# Miscellaneous.net
KiCad netlist of a schematic drawn in Altium Designer
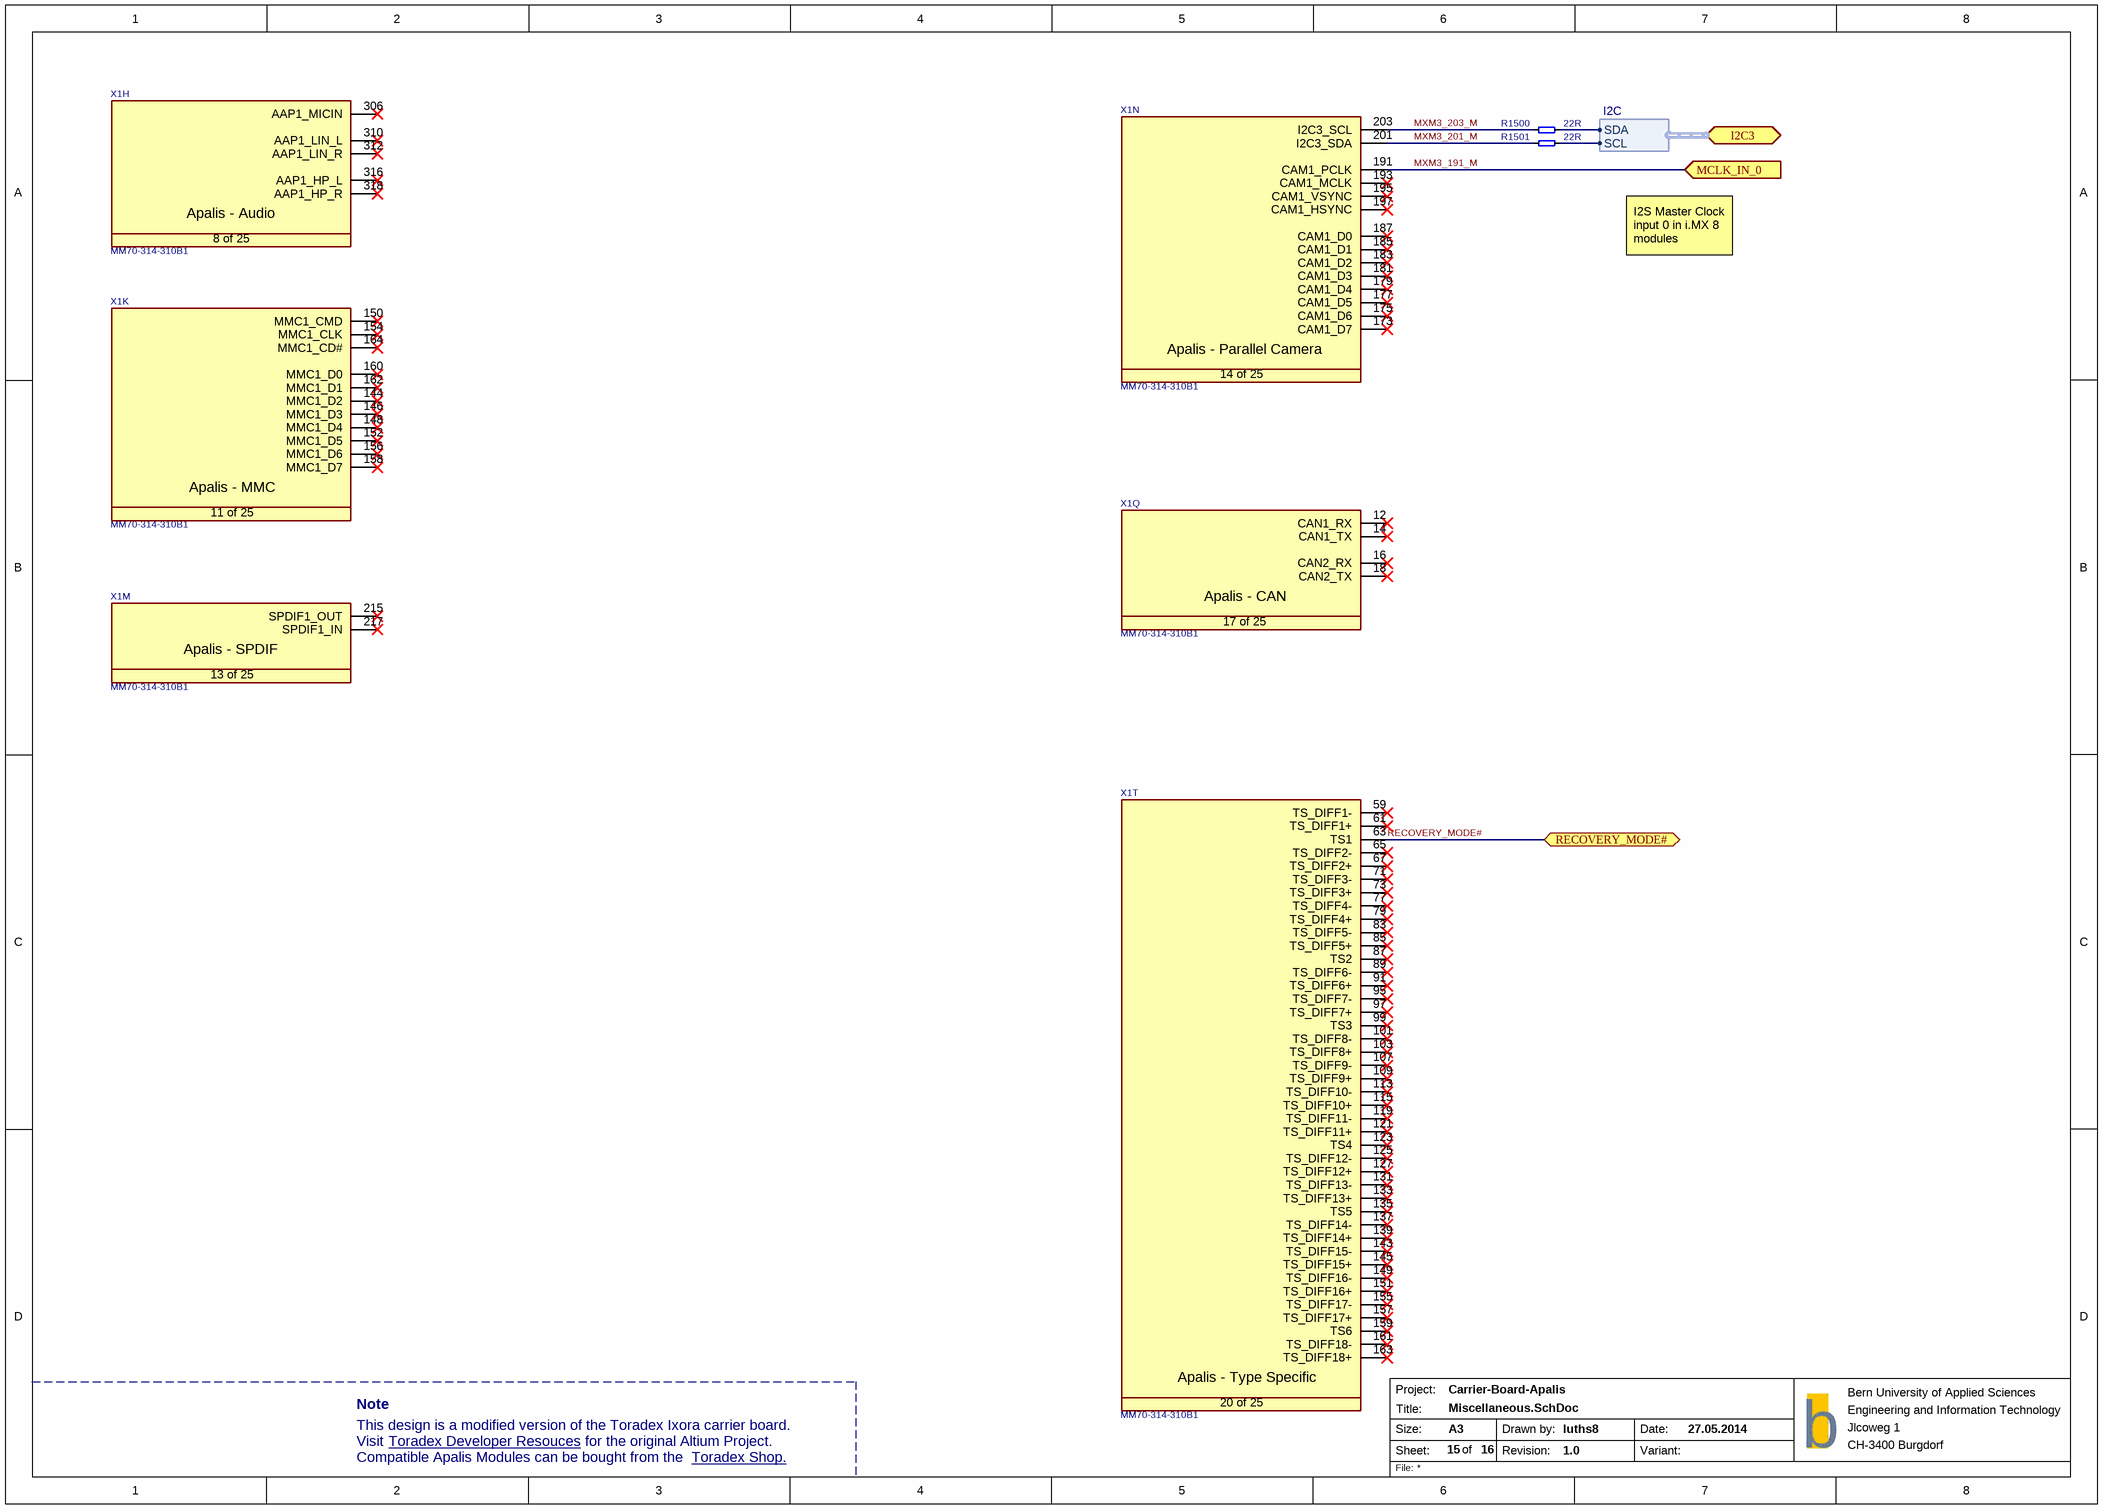
[diagram p0: Miscellaneous.SchDoc]

(export (version "E")
  (design (tool "Eeschema 10.0.6"))
  (components
    (comp (ref "R1500")
      (value "22R")
      (footprint "SMD0603RES")
      (description "Resistor 22 ohm 63mW 5% 0603")
      (fields (field (name "TOLERANCE") "5%"))
      (libsource (lib "Ixora") (part "R-22R-63mW-5%-0402"))
    )
    (comp (ref "R1501")
      (value "22R")
      (footprint "SMD0603RES")
      (description "Resistor 22 ohm 63mW 5% 0603")
      (fields (field (name "TOLERANCE") "5%"))
      (libsource (lib "Ixora") (part "R-22R-63mW-5%-0402"))
    )
    (comp (ref "X1")
      (value "CON-JAE-MM70-314-310B1-314-0.5mm")
      (footprint "T_JAE_MM70-314-310B1")
      (description "MXM3 Connector")
      (fields (field (name "MANUFACTURER PART NO.") "MM70-314-310B1"))
      (libsource (lib "Ixora") (part "CON-JAE-MM70-314-310B1-314-0.5mm"))
    )
  )
  (nets
    (net (code "2") (name "/MXM3_191_M") (class "Default")
      (node (ref "X1") (pin "191") (pinfunction "CAM1_PCLK_191") (pintype "passive"))
    )
    (net (code "3") (name "/MXM3_201_M") (class "Default")
      (node (ref "R1501") (pin "1") (pinfunction "1_1") (pintype "passive"))
      (node (ref "X1") (pin "201") (pinfunction "I2C3_SDA_201") (pintype "passive"))
    )
    (net (code "4") (name "/MXM3_203_M") (class "Default")
      (node (ref "R1500") (pin "1") (pinfunction "1_1") (pintype "passive"))
      (node (ref "X1") (pin "203") (pinfunction "I2C3_SCL_203") (pintype "passive"))
    )
    (net (code "5") (name "/RECOVERY_MODE#") (class "Default")
      (node (ref "X1") (pin "63") (pinfunction "TS1_63") (pintype "passive"))
    )
    (net (code "6") (name "/SCL") (class "Default")
      (node (ref "R1501") (pin "2") (pinfunction "2_2") (pintype "passive"))
    )
    (net (code "7") (name "/SDA") (class "Default")
      (node (ref "R1500") (pin "2") (pinfunction "2_2") (pintype "passive"))
    )
    (net (code "9") (name "unconnected-(X1H-AAP1_HP_L-Pad316)") (class "Default")
      (node (ref "X1") (pin "316") (pinfunction "AAP1_HP_L_316") (pintype "passive+no_connect"))
    )
    (net (code "10") (name "unconnected-(X1H-AAP1_HP_R-Pad318)") (class "Default")
      (node (ref "X1") (pin "318") (pinfunction "AAP1_HP_R_318") (pintype "passive+no_connect"))
    )
    (net (code "11") (name "unconnected-(X1H-AAP1_LIN_L-Pad310)") (class "Default")
      (node (ref "X1") (pin "310") (pinfunction "AAP1_LIN_L_310") (pintype "passive+no_connect"))
    )
    (net (code "12") (name "unconnected-(X1H-AAP1_LIN_R-Pad312)") (class "Default")
      (node (ref "X1") (pin "312") (pinfunction "AAP1_LIN_R_312") (pintype "passive+no_connect"))
    )
    (net (code "13") (name "unconnected-(X1H-AAP1_MICIN-Pad306)") (class "Default")
      (node (ref "X1") (pin "306") (pinfunction "AAP1_MICIN_306") (pintype "passive+no_connect"))
    )
    (net (code "14") (name "unconnected-(X1K-MMC1_CD#-Pad164)") (class "Default")
      (node (ref "X1") (pin "164") (pinfunction "MMC1_CD#_164") (pintype "passive+no_connect"))
    )
    (net (code "15") (name "unconnected-(X1K-MMC1_CLK-Pad154)") (class "Default")
      (node (ref "X1") (pin "154") (pinfunction "MMC1_CLK_154") (pintype "passive+no_connect"))
    )
    (net (code "16") (name "unconnected-(X1K-MMC1_CMD-Pad150)") (class "Default")
      (node (ref "X1") (pin "150") (pinfunction "MMC1_CMD_150") (pintype "passive+no_connect"))
    )
    (net (code "17") (name "unconnected-(X1K-MMC1_D0-Pad160)") (class "Default")
      (node (ref "X1") (pin "160") (pinfunction "MMC1_D0_160") (pintype "passive+no_connect"))
    )
    (net (code "18") (name "unconnected-(X1K-MMC1_D1-Pad162)") (class "Default")
      (node (ref "X1") (pin "162") (pinfunction "MMC1_D1_162") (pintype "passive+no_connect"))
    )
    (net (code "19") (name "unconnected-(X1K-MMC1_D2-Pad144)") (class "Default")
      (node (ref "X1") (pin "144") (pinfunction "MMC1_D2_144") (pintype "passive+no_connect"))
    )
    (net (code "20") (name "unconnected-(X1K-MMC1_D3-Pad146)") (class "Default")
      (node (ref "X1") (pin "146") (pinfunction "MMC1_D3_146") (pintype "passive+no_connect"))
    )
    (net (code "21") (name "unconnected-(X1K-MMC1_D4-Pad148)") (class "Default")
      (node (ref "X1") (pin "148") (pinfunction "MMC1_D4_148") (pintype "passive+no_connect"))
    )
    (net (code "22") (name "unconnected-(X1K-MMC1_D5-Pad152)") (class "Default")
      (node (ref "X1") (pin "152") (pinfunction "MMC1_D5_152") (pintype "passive+no_connect"))
    )
    (net (code "23") (name "unconnected-(X1K-MMC1_D6-Pad156)") (class "Default")
      (node (ref "X1") (pin "156") (pinfunction "MMC1_D6_156") (pintype "passive+no_connect"))
    )
    (net (code "24") (name "unconnected-(X1K-MMC1_D7-Pad158)") (class "Default")
      (node (ref "X1") (pin "158") (pinfunction "MMC1_D7_158") (pintype "passive+no_connect"))
    )
    (net (code "25") (name "unconnected-(X1M-SPDIF1_IN-Pad217)") (class "Default")
      (node (ref "X1") (pin "217") (pinfunction "SPDIF1_IN_217") (pintype "passive+no_connect"))
    )
    (net (code "26") (name "unconnected-(X1M-SPDIF1_OUT-Pad215)") (class "Default")
      (node (ref "X1") (pin "215") (pinfunction "SPDIF1_OUT_215") (pintype "passive+no_connect"))
    )
    (net (code "27") (name "unconnected-(X1N-CAM1_D0-Pad187)") (class "Default")
      (node (ref "X1") (pin "187") (pinfunction "CAM1_D0_187") (pintype "passive+no_connect"))
    )
    (net (code "28") (name "unconnected-(X1N-CAM1_D1-Pad185)") (class "Default")
      (node (ref "X1") (pin "185") (pinfunction "CAM1_D1_185") (pintype "passive+no_connect"))
    )
    (net (code "29") (name "unconnected-(X1N-CAM1_D2-Pad183)") (class "Default")
      (node (ref "X1") (pin "183") (pinfunction "CAM1_D2_183") (pintype "passive+no_connect"))
    )
    (net (code "30") (name "unconnected-(X1N-CAM1_D3-Pad181)") (class "Default")
      (node (ref "X1") (pin "181") (pinfunction "CAM1_D3_181") (pintype "passive+no_connect"))
    )
    (net (code "31") (name "unconnected-(X1N-CAM1_D4-Pad179)") (class "Default")
      (node (ref "X1") (pin "179") (pinfunction "CAM1_D4_179") (pintype "passive+no_connect"))
    )
    (net (code "32") (name "unconnected-(X1N-CAM1_D5-Pad177)") (class "Default")
      (node (ref "X1") (pin "177") (pinfunction "CAM1_D5_177") (pintype "passive+no_connect"))
    )
    (net (code "33") (name "unconnected-(X1N-CAM1_D6-Pad175)") (class "Default")
      (node (ref "X1") (pin "175") (pinfunction "CAM1_D6_175") (pintype "passive+no_connect"))
    )
    (net (code "34") (name "unconnected-(X1N-CAM1_D7-Pad173)") (class "Default")
      (node (ref "X1") (pin "173") (pinfunction "CAM1_D7_173") (pintype "passive+no_connect"))
    )
    (net (code "35") (name "unconnected-(X1N-CAM1_HSYNC-Pad197)") (class "Default")
      (node (ref "X1") (pin "197") (pinfunction "CAM1_HSYNC_197") (pintype "passive+no_connect"))
    )
    (net (code "36") (name "unconnected-(X1N-CAM1_MCLK-Pad193)") (class "Default")
      (node (ref "X1") (pin "193") (pinfunction "CAM1_MCLK_193") (pintype "passive+no_connect"))
    )
    (net (code "37") (name "unconnected-(X1N-CAM1_VSYNC-Pad195)") (class "Default")
      (node (ref "X1") (pin "195") (pinfunction "CAM1_VSYNC_195") (pintype "passive+no_connect"))
    )
    (net (code "38") (name "unconnected-(X1Q-CAN1_RX-Pad12)") (class "Default")
      (node (ref "X1") (pin "12") (pinfunction "CAN1_RX_12") (pintype "passive+no_connect"))
    )
    (net (code "39") (name "unconnected-(X1Q-CAN1_TX-Pad14)") (class "Default")
      (node (ref "X1") (pin "14") (pinfunction "CAN1_TX_14") (pintype "passive+no_connect"))
    )
    (net (code "40") (name "unconnected-(X1Q-CAN2_RX-Pad16)") (class "Default")
      (node (ref "X1") (pin "16") (pinfunction "CAN2_RX_16") (pintype "passive+no_connect"))
    )
    (net (code "41") (name "unconnected-(X1Q-CAN2_TX-Pad18)") (class "Default")
      (node (ref "X1") (pin "18") (pinfunction "CAN2_TX_18") (pintype "passive+no_connect"))
    )
    (net (code "42") (name "unconnected-(X1T-TS2-Pad87)") (class "Default")
      (node (ref "X1") (pin "87") (pinfunction "TS2_87") (pintype "passive+no_connect"))
    )
    (net (code "43") (name "unconnected-(X1T-TS3-Pad99)") (class "Default")
      (node (ref "X1") (pin "99") (pinfunction "TS3_99") (pintype "passive+no_connect"))
    )
    (net (code "44") (name "unconnected-(X1T-TS4-Pad123)") (class "Default")
      (node (ref "X1") (pin "123") (pinfunction "TS4_123") (pintype "passive+no_connect"))
    )
    (net (code "45") (name "unconnected-(X1T-TS5-Pad135)") (class "Default")
      (node (ref "X1") (pin "135") (pinfunction "TS5_135") (pintype "passive+no_connect"))
    )
    (net (code "46") (name "unconnected-(X1T-TS6-Pad159)") (class "Default")
      (node (ref "X1") (pin "159") (pinfunction "TS6_159") (pintype "passive+no_connect"))
    )
    (net (code "47") (name "unconnected-(X1T-TS_DIFF1+-Pad61)") (class "Default")
      (node (ref "X1") (pin "61") (pinfunction "TS_DIFF1+_61") (pintype "passive+no_connect"))
    )
    (net (code "48") (name "unconnected-(X1T-TS_DIFF1--Pad59)") (class "Default")
      (node (ref "X1") (pin "59") (pinfunction "TS_DIFF1-_59") (pintype "passive+no_connect"))
    )
    (net (code "49") (name "unconnected-(X1T-TS_DIFF2+-Pad67)") (class "Default")
      (node (ref "X1") (pin "67") (pinfunction "TS_DIFF2+_67") (pintype "passive+no_connect"))
    )
    (net (code "50") (name "unconnected-(X1T-TS_DIFF2--Pad65)") (class "Default")
      (node (ref "X1") (pin "65") (pinfunction "TS_DIFF2-_65") (pintype "passive+no_connect"))
    )
    (net (code "51") (name "unconnected-(X1T-TS_DIFF3+-Pad73)") (class "Default")
      (node (ref "X1") (pin "73") (pinfunction "TS_DIFF3+_73") (pintype "passive+no_connect"))
    )
    (net (code "52") (name "unconnected-(X1T-TS_DIFF3--Pad71)") (class "Default")
      (node (ref "X1") (pin "71") (pinfunction "TS_DIFF3-_71") (pintype "passive+no_connect"))
    )
    (net (code "53") (name "unconnected-(X1T-TS_DIFF4+-Pad79)") (class "Default")
      (node (ref "X1") (pin "79") (pinfunction "TS_DIFF4+_79") (pintype "passive+no_connect"))
    )
    (net (code "54") (name "unconnected-(X1T-TS_DIFF4--Pad77)") (class "Default")
      (node (ref "X1") (pin "77") (pinfunction "TS_DIFF4-_77") (pintype "passive+no_connect"))
    )
    (net (code "55") (name "unconnected-(X1T-TS_DIFF5+-Pad85)") (class "Default")
      (node (ref "X1") (pin "85") (pinfunction "TS_DIFF5+_85") (pintype "passive+no_connect"))
    )
    (net (code "56") (name "unconnected-(X1T-TS_DIFF5--Pad83)") (class "Default")
      (node (ref "X1") (pin "83") (pinfunction "TS_DIFF5-_83") (pintype "passive+no_connect"))
    )
    (net (code "57") (name "unconnected-(X1T-TS_DIFF6+-Pad91)") (class "Default")
      (node (ref "X1") (pin "91") (pinfunction "TS_DIFF6+_91") (pintype "passive+no_connect"))
    )
    (net (code "58") (name "unconnected-(X1T-TS_DIFF6--Pad89)") (class "Default")
      (node (ref "X1") (pin "89") (pinfunction "TS_DIFF6-_89") (pintype "passive+no_connect"))
    )
    (net (code "59") (name "unconnected-(X1T-TS_DIFF7+-Pad97)") (class "Default")
      (node (ref "X1") (pin "97") (pinfunction "TS_DIFF7+_97") (pintype "passive+no_connect"))
    )
    (net (code "60") (name "unconnected-(X1T-TS_DIFF7--Pad95)") (class "Default")
      (node (ref "X1") (pin "95") (pinfunction "TS_DIFF7-_95") (pintype "passive+no_connect"))
    )
    (net (code "61") (name "unconnected-(X1T-TS_DIFF8+-Pad103)") (class "Default")
      (node (ref "X1") (pin "103") (pinfunction "TS_DIFF8+_103") (pintype "passive+no_connect"))
    )
    (net (code "62") (name "unconnected-(X1T-TS_DIFF8--Pad101)") (class "Default")
      (node (ref "X1") (pin "101") (pinfunction "TS_DIFF8-_101") (pintype "passive+no_connect"))
    )
    (net (code "63") (name "unconnected-(X1T-TS_DIFF9+-Pad109)") (class "Default")
      (node (ref "X1") (pin "109") (pinfunction "TS_DIFF9+_109") (pintype "passive+no_connect"))
    )
    (net (code "64") (name "unconnected-(X1T-TS_DIFF9--Pad107)") (class "Default")
      (node (ref "X1") (pin "107") (pinfunction "TS_DIFF9-_107") (pintype "passive+no_connect"))
    )
    (net (code "65") (name "unconnected-(X1T-TS_DIFF10+-Pad115)") (class "Default")
      (node (ref "X1") (pin "115") (pinfunction "TS_DIFF10+_115") (pintype "passive+no_connect"))
    )
    (net (code "66") (name "unconnected-(X1T-TS_DIFF10--Pad113)") (class "Default")
      (node (ref "X1") (pin "113") (pinfunction "TS_DIFF10-_113") (pintype "passive+no_connect"))
    )
    (net (code "67") (name "unconnected-(X1T-TS_DIFF11+-Pad121)") (class "Default")
      (node (ref "X1") (pin "121") (pinfunction "TS_DIFF11+_121") (pintype "passive+no_connect"))
    )
    (net (code "68") (name "unconnected-(X1T-TS_DIFF11--Pad119)") (class "Default")
      (node (ref "X1") (pin "119") (pinfunction "TS_DIFF11-_119") (pintype "passive+no_connect"))
    )
    (net (code "69") (name "unconnected-(X1T-TS_DIFF12+-Pad127)") (class "Default")
      (node (ref "X1") (pin "127") (pinfunction "TS_DIFF12+_127") (pintype "passive+no_connect"))
    )
    (net (code "70") (name "unconnected-(X1T-TS_DIFF12--Pad125)") (class "Default")
      (node (ref "X1") (pin "125") (pinfunction "TS_DIFF12-_125") (pintype "passive+no_connect"))
    )
    (net (code "71") (name "unconnected-(X1T-TS_DIFF13+-Pad133)") (class "Default")
      (node (ref "X1") (pin "133") (pinfunction "TS_DIFF13+_133") (pintype "passive+no_connect"))
    )
    (net (code "72") (name "unconnected-(X1T-TS_DIFF13--Pad131)") (class "Default")
      (node (ref "X1") (pin "131") (pinfunction "TS_DIFF13-_131") (pintype "passive+no_connect"))
    )
    (net (code "73") (name "unconnected-(X1T-TS_DIFF14+-Pad139)") (class "Default")
      (node (ref "X1") (pin "139") (pinfunction "TS_DIFF14+_139") (pintype "passive+no_connect"))
    )
    (net (code "74") (name "unconnected-(X1T-TS_DIFF14--Pad137)") (class "Default")
      (node (ref "X1") (pin "137") (pinfunction "TS_DIFF14-_137") (pintype "passive+no_connect"))
    )
    (net (code "75") (name "unconnected-(X1T-TS_DIFF15+-Pad145)") (class "Default")
      (node (ref "X1") (pin "145") (pinfunction "TS_DIFF15+_145") (pintype "passive+no_connect"))
    )
    (net (code "76") (name "unconnected-(X1T-TS_DIFF15--Pad143)") (class "Default")
      (node (ref "X1") (pin "143") (pinfunction "TS_DIFF15-_143") (pintype "passive+no_connect"))
    )
    (net (code "77") (name "unconnected-(X1T-TS_DIFF16+-Pad151)") (class "Default")
      (node (ref "X1") (pin "151") (pinfunction "TS_DIFF16+_151") (pintype "passive+no_connect"))
    )
    (net (code "78") (name "unconnected-(X1T-TS_DIFF16--Pad149)") (class "Default")
      (node (ref "X1") (pin "149") (pinfunction "TS_DIFF16-_149") (pintype "passive+no_connect"))
    )
    (net (code "79") (name "unconnected-(X1T-TS_DIFF17+-Pad157)") (class "Default")
      (node (ref "X1") (pin "157") (pinfunction "TS_DIFF17+_157") (pintype "passive+no_connect"))
    )
    (net (code "80") (name "unconnected-(X1T-TS_DIFF17--Pad155)") (class "Default")
      (node (ref "X1") (pin "155") (pinfunction "TS_DIFF17-_155") (pintype "passive+no_connect"))
    )
    (net (code "81") (name "unconnected-(X1T-TS_DIFF18+-Pad163)") (class "Default")
      (node (ref "X1") (pin "163") (pinfunction "TS_DIFF18+_163") (pintype "passive+no_connect"))
    )
    (net (code "82") (name "unconnected-(X1T-TS_DIFF18--Pad161)") (class "Default")
      (node (ref "X1") (pin "161") (pinfunction "TS_DIFF18-_161") (pintype "passive+no_connect"))
    )
  )
)
